# w.net
KiCad netlist of a schematic drawn in EAGLE
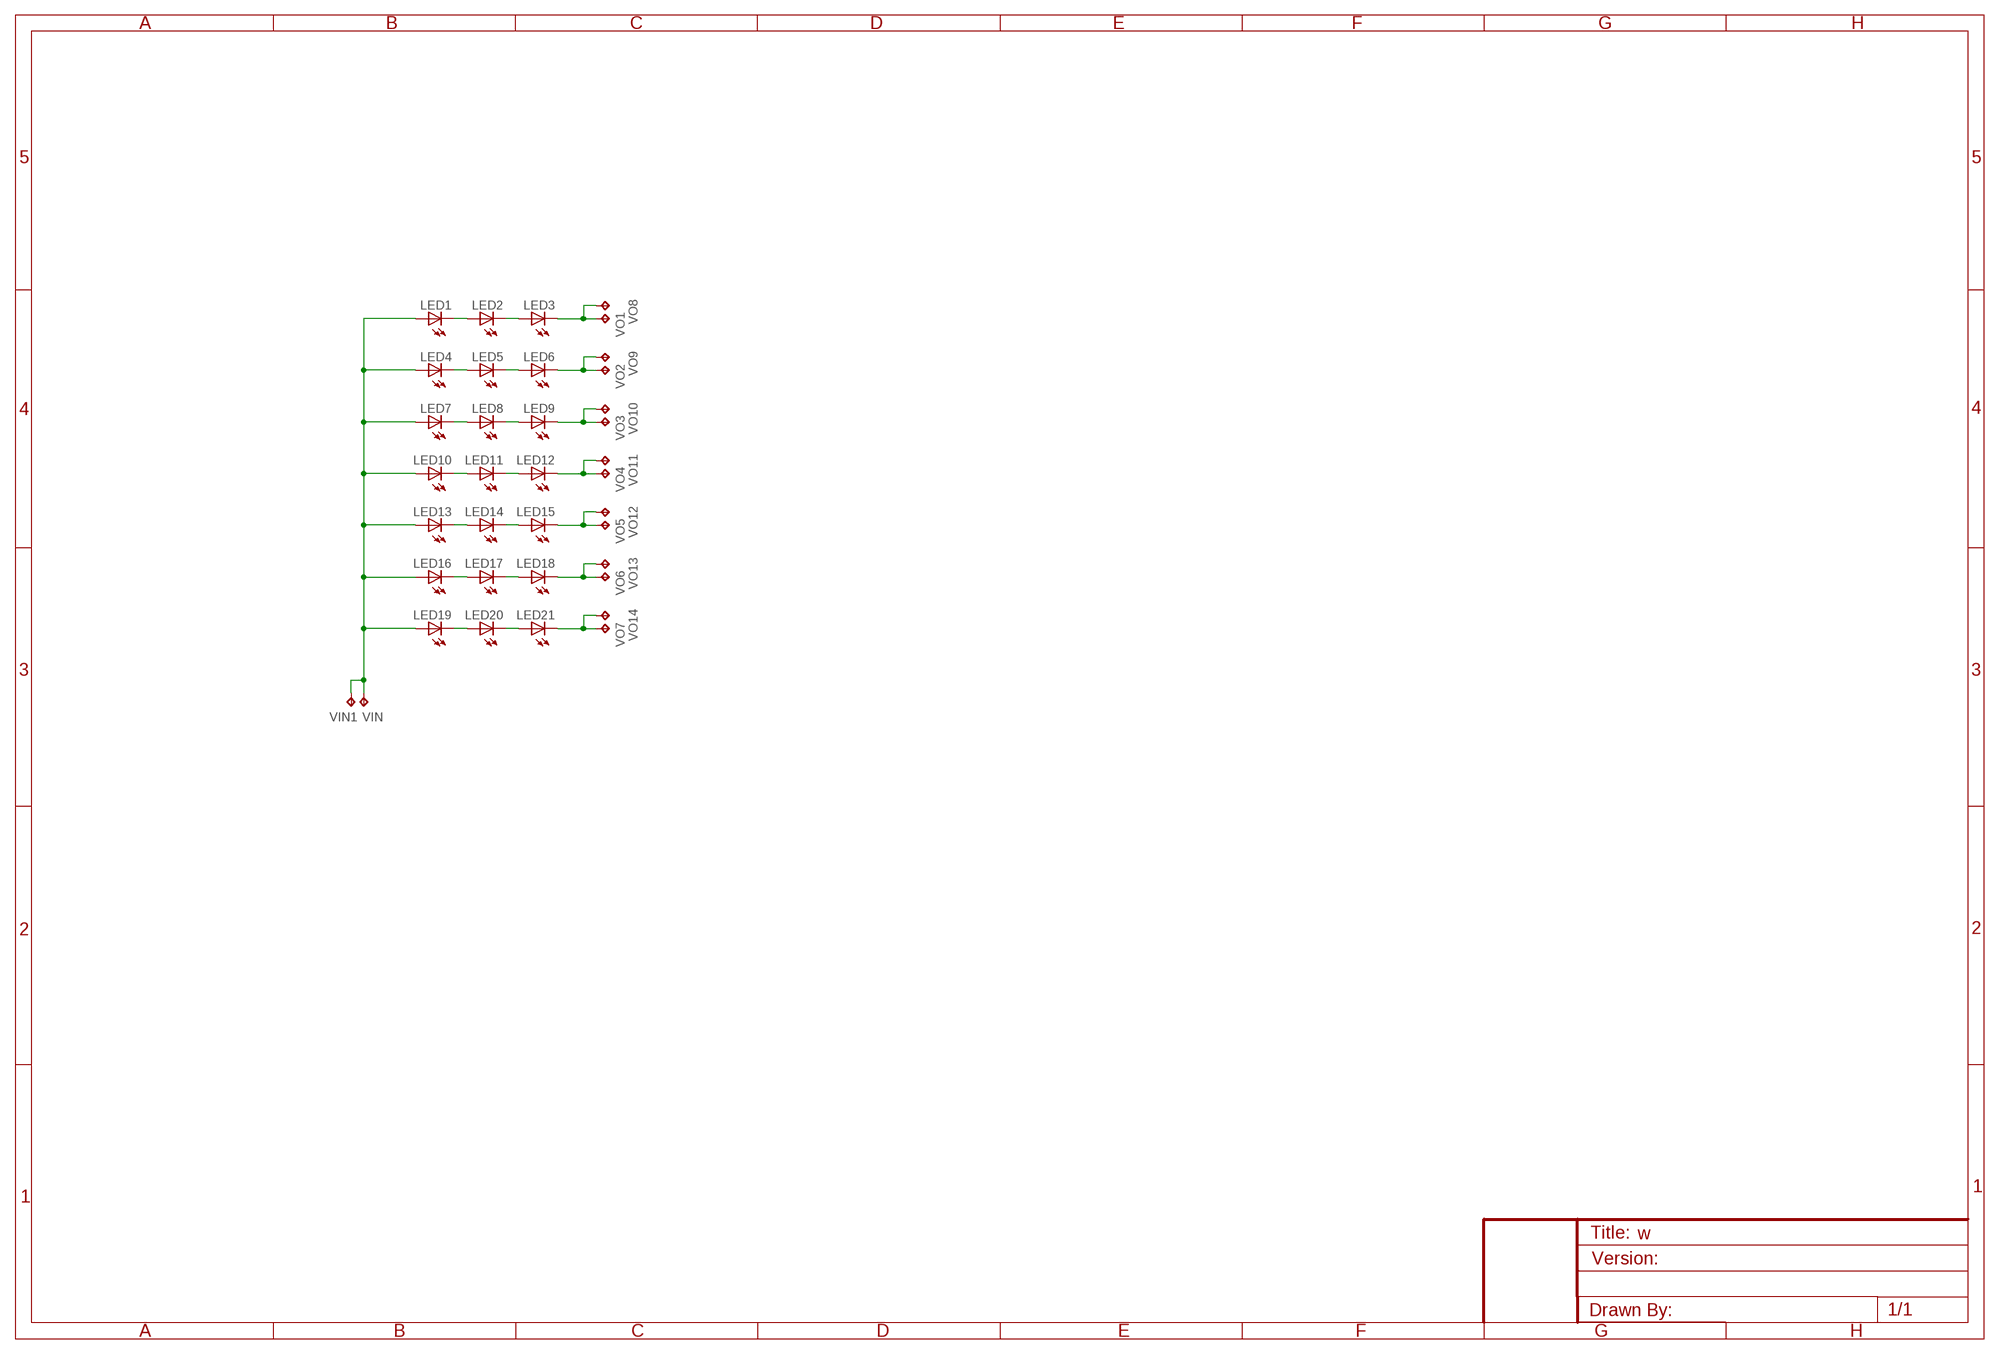
[diagram p0: schematic, sheet 1]

(export (version "E")
  (design (tool "Eeschema 10.0.6"))
  (components
    (comp (ref "LED1")
      (value "LED0805")
      (footprint "eagle-import:LED_0805")
      (libsource (lib "eagle-import") (part "LED0805"))
    )
    (comp (ref "LED2")
      (value "LED0805")
      (footprint "eagle-import:LED_0805")
      (libsource (lib "eagle-import") (part "LED0805"))
    )
    (comp (ref "LED3")
      (value "LED0805")
      (footprint "eagle-import:LED_0805")
      (libsource (lib "eagle-import") (part "LED0805"))
    )
    (comp (ref "LED4")
      (value "LED0805")
      (footprint "eagle-import:LED_0805")
      (libsource (lib "eagle-import") (part "LED0805"))
    )
    (comp (ref "LED5")
      (value "LED0805")
      (footprint "eagle-import:LED_0805")
      (libsource (lib "eagle-import") (part "LED0805"))
    )
    (comp (ref "LED6")
      (value "LED0805")
      (footprint "eagle-import:LED_0805")
      (libsource (lib "eagle-import") (part "LED0805"))
    )
    (comp (ref "LED7")
      (value "LED0805")
      (footprint "eagle-import:LED_0805")
      (libsource (lib "eagle-import") (part "LED0805"))
    )
    (comp (ref "LED8")
      (value "LED0805")
      (footprint "eagle-import:LED_0805")
      (libsource (lib "eagle-import") (part "LED0805"))
    )
    (comp (ref "LED9")
      (value "LED0805")
      (footprint "eagle-import:LED_0805")
      (libsource (lib "eagle-import") (part "LED0805"))
    )
    (comp (ref "LED10")
      (value "LED0805")
      (footprint "eagle-import:LED_0805")
      (libsource (lib "eagle-import") (part "LED0805"))
    )
    (comp (ref "LED11")
      (value "LED0805")
      (footprint "eagle-import:LED_0805")
      (libsource (lib "eagle-import") (part "LED0805"))
    )
    (comp (ref "LED12")
      (value "LED0805")
      (footprint "eagle-import:LED_0805")
      (libsource (lib "eagle-import") (part "LED0805"))
    )
    (comp (ref "LED13")
      (value "LED0805")
      (footprint "eagle-import:LED_0805")
      (libsource (lib "eagle-import") (part "LED0805"))
    )
    (comp (ref "LED14")
      (value "LED0805")
      (footprint "eagle-import:LED_0805")
      (libsource (lib "eagle-import") (part "LED0805"))
    )
    (comp (ref "LED15")
      (value "LED0805")
      (footprint "eagle-import:LED_0805")
      (libsource (lib "eagle-import") (part "LED0805"))
    )
    (comp (ref "LED16")
      (value "LED0805")
      (footprint "eagle-import:LED_0805")
      (libsource (lib "eagle-import") (part "LED0805"))
    )
    (comp (ref "LED17")
      (value "LED0805")
      (footprint "eagle-import:LED_0805")
      (libsource (lib "eagle-import") (part "LED0805"))
    )
    (comp (ref "LED18")
      (value "LED0805")
      (footprint "eagle-import:LED_0805")
      (libsource (lib "eagle-import") (part "LED0805"))
    )
    (comp (ref "LED19")
      (value "LED0805")
      (footprint "eagle-import:LED_0805")
      (libsource (lib "eagle-import") (part "LED0805"))
    )
    (comp (ref "LED20")
      (value "LED0805")
      (footprint "eagle-import:LED_0805")
      (libsource (lib "eagle-import") (part "LED0805"))
    )
    (comp (ref "LED21")
      (value "LED0805")
      (footprint "eagle-import:LED_0805")
      (libsource (lib "eagle-import") (part "LED0805"))
    )
    (comp (ref "VIN")
      (value "TEST_POINTPAD1-20")
      (footprint "eagle-import:P1-20")
      (libsource (lib "eagle-import") (part "TEST_POINTPAD1-20"))
    )
    (comp (ref "VIN1")
      (value "TEST_POINTPAD1-20")
      (footprint "eagle-import:P1-20")
      (libsource (lib "eagle-import") (part "TEST_POINTPAD1-20"))
    )
    (comp (ref "VO1")
      (value "TEST_POINTPAD1-20")
      (footprint "eagle-import:P1-20")
      (libsource (lib "eagle-import") (part "TEST_POINTPAD1-20"))
    )
    (comp (ref "VO2")
      (value "TEST_POINTPAD1-20")
      (footprint "eagle-import:P1-20")
      (libsource (lib "eagle-import") (part "TEST_POINTPAD1-20"))
    )
    (comp (ref "VO3")
      (value "TEST_POINTPAD1-20")
      (footprint "eagle-import:P1-20")
      (libsource (lib "eagle-import") (part "TEST_POINTPAD1-20"))
    )
    (comp (ref "VO4")
      (value "TEST_POINTPAD1-20")
      (footprint "eagle-import:P1-20")
      (libsource (lib "eagle-import") (part "TEST_POINTPAD1-20"))
    )
    (comp (ref "VO5")
      (value "TEST_POINTPAD1-20")
      (footprint "eagle-import:P1-20")
      (libsource (lib "eagle-import") (part "TEST_POINTPAD1-20"))
    )
    (comp (ref "VO6")
      (value "TEST_POINTPAD1-20")
      (footprint "eagle-import:P1-20")
      (libsource (lib "eagle-import") (part "TEST_POINTPAD1-20"))
    )
    (comp (ref "VO7")
      (value "TEST_POINTPAD1-20")
      (footprint "eagle-import:P1-20")
      (libsource (lib "eagle-import") (part "TEST_POINTPAD1-20"))
    )
    (comp (ref "VO8")
      (value "TEST_POINTPAD1-20")
      (footprint "eagle-import:P1-20")
      (libsource (lib "eagle-import") (part "TEST_POINTPAD1-20"))
    )
    (comp (ref "VO9")
      (value "TEST_POINTPAD1-20")
      (footprint "eagle-import:P1-20")
      (libsource (lib "eagle-import") (part "TEST_POINTPAD1-20"))
    )
    (comp (ref "VO10")
      (value "TEST_POINTPAD1-20")
      (footprint "eagle-import:P1-20")
      (libsource (lib "eagle-import") (part "TEST_POINTPAD1-20"))
    )
    (comp (ref "VO11")
      (value "TEST_POINTPAD1-20")
      (footprint "eagle-import:P1-20")
      (libsource (lib "eagle-import") (part "TEST_POINTPAD1-20"))
    )
    (comp (ref "VO12")
      (value "TEST_POINTPAD1-20")
      (footprint "eagle-import:P1-20")
      (libsource (lib "eagle-import") (part "TEST_POINTPAD1-20"))
    )
    (comp (ref "VO13")
      (value "TEST_POINTPAD1-20")
      (footprint "eagle-import:P1-20")
      (libsource (lib "eagle-import") (part "TEST_POINTPAD1-20"))
    )
    (comp (ref "VO14")
      (value "TEST_POINTPAD1-20")
      (footprint "eagle-import:P1-20")
      (libsource (lib "eagle-import") (part "TEST_POINTPAD1-20"))
    )
  )
  (nets
    (net (code "1") (name "Net-(LED1-PadA)") (class "Default")
      (node (ref "LED1") (pin "A") (pinfunction "A_A") (pintype "passive"))
      (node (ref "LED10") (pin "A") (pinfunction "A_A") (pintype "passive"))
      (node (ref "LED13") (pin "A") (pinfunction "A_A") (pintype "passive"))
      (node (ref "LED16") (pin "A") (pinfunction "A_A") (pintype "passive"))
      (node (ref "LED19") (pin "A") (pinfunction "A_A") (pintype "passive"))
      (node (ref "LED4") (pin "A") (pinfunction "A_A") (pintype "passive"))
      (node (ref "LED7") (pin "A") (pinfunction "A_A") (pintype "passive"))
      (node (ref "VIN") (pin "TP") (pinfunction "TP_TP") (pintype "input"))
      (node (ref "VIN1") (pin "TP") (pinfunction "TP_TP") (pintype "input"))
    )
    (net (code "2") (name "Net-(LED1-PadC)") (class "Default")
      (node (ref "LED1") (pin "C") (pinfunction "C_C") (pintype "passive"))
      (node (ref "LED2") (pin "A") (pinfunction "A_A") (pintype "passive"))
    )
    (net (code "3") (name "Net-(LED2-PadC)") (class "Default")
      (node (ref "LED2") (pin "C") (pinfunction "C_C") (pintype "passive"))
      (node (ref "LED3") (pin "A") (pinfunction "A_A") (pintype "passive"))
    )
    (net (code "4") (name "Net-(LED3-PadC)") (class "Default")
      (node (ref "LED3") (pin "C") (pinfunction "C_C") (pintype "passive"))
      (node (ref "VO1") (pin "TP") (pinfunction "TP_TP") (pintype "input"))
      (node (ref "VO8") (pin "TP") (pinfunction "TP_TP") (pintype "input"))
    )
    (net (code "5") (name "Net-(LED4-PadC)") (class "Default")
      (node (ref "LED4") (pin "C") (pinfunction "C_C") (pintype "passive"))
      (node (ref "LED5") (pin "A") (pinfunction "A_A") (pintype "passive"))
    )
    (net (code "6") (name "Net-(LED5-PadC)") (class "Default")
      (node (ref "LED5") (pin "C") (pinfunction "C_C") (pintype "passive"))
      (node (ref "LED6") (pin "A") (pinfunction "A_A") (pintype "passive"))
    )
    (net (code "7") (name "Net-(LED6-PadC)") (class "Default")
      (node (ref "LED6") (pin "C") (pinfunction "C_C") (pintype "passive"))
      (node (ref "VO2") (pin "TP") (pinfunction "TP_TP") (pintype "input"))
      (node (ref "VO9") (pin "TP") (pinfunction "TP_TP") (pintype "input"))
    )
    (net (code "8") (name "Net-(LED7-PadC)") (class "Default")
      (node (ref "LED7") (pin "C") (pinfunction "C_C") (pintype "passive"))
      (node (ref "LED8") (pin "A") (pinfunction "A_A") (pintype "passive"))
    )
    (net (code "9") (name "Net-(LED8-PadC)") (class "Default")
      (node (ref "LED8") (pin "C") (pinfunction "C_C") (pintype "passive"))
      (node (ref "LED9") (pin "A") (pinfunction "A_A") (pintype "passive"))
    )
    (net (code "10") (name "Net-(LED9-PadC)") (class "Default")
      (node (ref "LED9") (pin "C") (pinfunction "C_C") (pintype "passive"))
      (node (ref "VO10") (pin "TP") (pinfunction "TP_TP") (pintype "input"))
      (node (ref "VO3") (pin "TP") (pinfunction "TP_TP") (pintype "input"))
    )
    (net (code "11") (name "Net-(LED10-PadC)") (class "Default")
      (node (ref "LED10") (pin "C") (pinfunction "C_C") (pintype "passive"))
      (node (ref "LED11") (pin "A") (pinfunction "A_A") (pintype "passive"))
    )
    (net (code "12") (name "Net-(LED11-PadC)") (class "Default")
      (node (ref "LED11") (pin "C") (pinfunction "C_C") (pintype "passive"))
      (node (ref "LED12") (pin "A") (pinfunction "A_A") (pintype "passive"))
    )
    (net (code "13") (name "Net-(LED12-PadC)") (class "Default")
      (node (ref "LED12") (pin "C") (pinfunction "C_C") (pintype "passive"))
      (node (ref "VO11") (pin "TP") (pinfunction "TP_TP") (pintype "input"))
      (node (ref "VO4") (pin "TP") (pinfunction "TP_TP") (pintype "input"))
    )
    (net (code "14") (name "Net-(LED13-PadC)") (class "Default")
      (node (ref "LED13") (pin "C") (pinfunction "C_C") (pintype "passive"))
      (node (ref "LED14") (pin "A") (pinfunction "A_A") (pintype "passive"))
    )
    (net (code "15") (name "Net-(LED14-PadC)") (class "Default")
      (node (ref "LED14") (pin "C") (pinfunction "C_C") (pintype "passive"))
      (node (ref "LED15") (pin "A") (pinfunction "A_A") (pintype "passive"))
    )
    (net (code "16") (name "Net-(LED15-PadC)") (class "Default")
      (node (ref "LED15") (pin "C") (pinfunction "C_C") (pintype "passive"))
      (node (ref "VO12") (pin "TP") (pinfunction "TP_TP") (pintype "input"))
      (node (ref "VO5") (pin "TP") (pinfunction "TP_TP") (pintype "input"))
    )
    (net (code "17") (name "Net-(LED16-PadC)") (class "Default")
      (node (ref "LED16") (pin "C") (pinfunction "C_C") (pintype "passive"))
      (node (ref "LED17") (pin "A") (pinfunction "A_A") (pintype "passive"))
    )
    (net (code "18") (name "Net-(LED17-PadC)") (class "Default")
      (node (ref "LED17") (pin "C") (pinfunction "C_C") (pintype "passive"))
      (node (ref "LED18") (pin "A") (pinfunction "A_A") (pintype "passive"))
    )
    (net (code "19") (name "Net-(LED18-PadC)") (class "Default")
      (node (ref "LED18") (pin "C") (pinfunction "C_C") (pintype "passive"))
      (node (ref "VO13") (pin "TP") (pinfunction "TP_TP") (pintype "input"))
      (node (ref "VO6") (pin "TP") (pinfunction "TP_TP") (pintype "input"))
    )
    (net (code "20") (name "Net-(LED19-PadC)") (class "Default")
      (node (ref "LED19") (pin "C") (pinfunction "C_C") (pintype "passive"))
      (node (ref "LED20") (pin "A") (pinfunction "A_A") (pintype "passive"))
    )
    (net (code "21") (name "Net-(LED20-PadC)") (class "Default")
      (node (ref "LED20") (pin "C") (pinfunction "C_C") (pintype "passive"))
      (node (ref "LED21") (pin "A") (pinfunction "A_A") (pintype "passive"))
    )
    (net (code "22") (name "Net-(LED21-PadC)") (class "Default")
      (node (ref "LED21") (pin "C") (pinfunction "C_C") (pintype "passive"))
      (node (ref "VO14") (pin "TP") (pinfunction "TP_TP") (pintype "input"))
      (node (ref "VO7") (pin "TP") (pinfunction "TP_TP") (pintype "input"))
    )
  )
)
